# vca.net
KiCad netlist of a schematic drawn in EAGLE
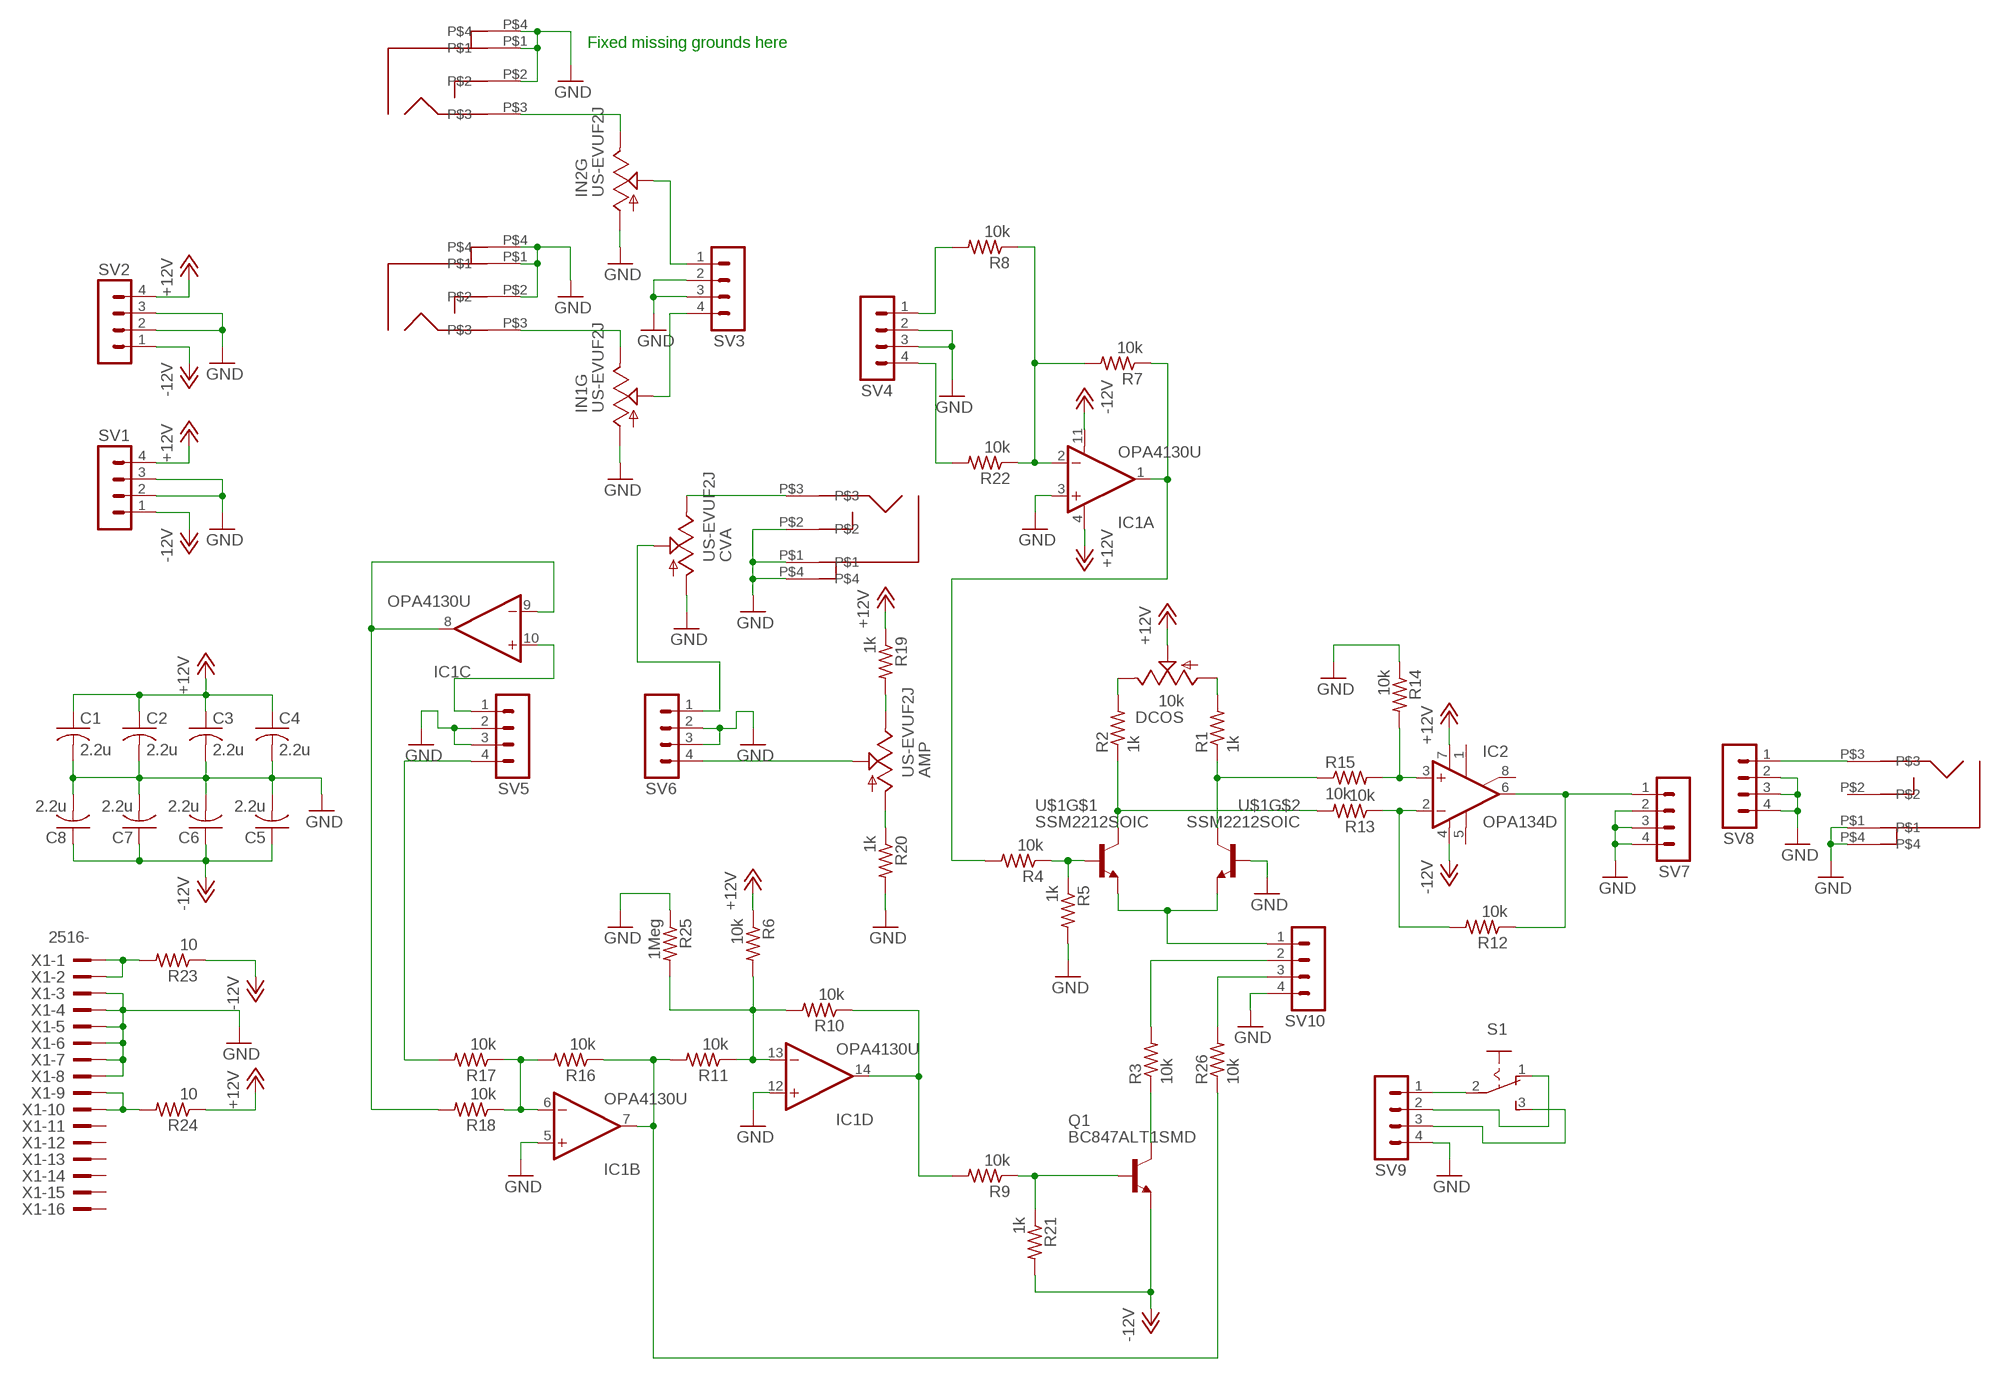
[diagram p0: schematic, sheet 1]

(export (version "E")
  (design (tool "Eeschema 10.0.6"))
  (components
    (comp (ref "AMP")
      (value "US-EVUF2J")
      (footprint "eagle-import:EVUFXJ")
      (libsource (lib "eagle-import") (part "US-EVUF2J"))
    )
    (comp (ref "C1")
      (value "2.2u")
      (footprint "eagle-import:C0603")
      (libsource (lib "eagle-import") (part "C-USC0603"))
    )
    (comp (ref "C2")
      (value "2.2u")
      (footprint "eagle-import:C0603")
      (libsource (lib "eagle-import") (part "C-USC0603"))
    )
    (comp (ref "C3")
      (value "2.2u")
      (footprint "eagle-import:C0603")
      (libsource (lib "eagle-import") (part "C-USC0603"))
    )
    (comp (ref "C4")
      (value "2.2u")
      (footprint "eagle-import:C0603")
      (libsource (lib "eagle-import") (part "C-USC0603"))
    )
    (comp (ref "C5")
      (value "2.2u")
      (footprint "eagle-import:C0603")
      (libsource (lib "eagle-import") (part "C-USC0603"))
    )
    (comp (ref "C6")
      (value "2.2u")
      (footprint "eagle-import:C0603")
      (libsource (lib "eagle-import") (part "C-USC0603"))
    )
    (comp (ref "C7")
      (value "2.2u")
      (footprint "eagle-import:C0603")
      (libsource (lib "eagle-import") (part "C-USC0603"))
    )
    (comp (ref "C8")
      (value "2.2u")
      (footprint "eagle-import:C0603")
      (libsource (lib "eagle-import") (part "C-USC0603"))
    )
    (comp (ref "CVA")
      (value "US-EVUF2J")
      (footprint "eagle-import:EVUFXJ")
      (libsource (lib "eagle-import") (part "US-EVUF2J"))
    )
    (comp (ref "CVIN")
      (value "PJ301BM")
      (footprint "eagle-import:PJ301BM")
      (libsource (lib "eagle-import") (part "PJ301BM"))
    )
    (comp (ref "DCOS")
      (value "10k")
      (footprint "eagle-import:RJ9W")
      (libsource (lib "eagle-import") (part "TRIM_US-RJ9W"))
    )
    (comp (ref "IC1")
      (value "OPA4130U")
      (footprint "eagle-import:SO14")
      (fields (field (name "MF") "TEXAS INSTRUMENTS") (field (name "MPN") "OPA4130UA"))
      (libsource (lib "eagle-import") (part "OPA4130U"))
    )
    (comp (ref "IC2")
      (value "OPA134D")
      (footprint "eagle-import:SO08")
      (libsource (lib "eagle-import") (part "OPA134D"))
    )
    (comp (ref "IN1")
      (value "PJ301BM")
      (footprint "eagle-import:PJ301BM")
      (libsource (lib "eagle-import") (part "PJ301BM"))
    )
    (comp (ref "IN1G")
      (value "US-EVUF2J")
      (footprint "eagle-import:EVUFXJ")
      (libsource (lib "eagle-import") (part "US-EVUF2J"))
    )
    (comp (ref "IN2")
      (value "PJ301BM")
      (footprint "eagle-import:PJ301BM")
      (libsource (lib "eagle-import") (part "PJ301BM"))
    )
    (comp (ref "IN2G")
      (value "US-EVUF2J")
      (footprint "eagle-import:EVUFXJ")
      (libsource (lib "eagle-import") (part "US-EVUF2J"))
    )
    (comp (ref "OUT")
      (value "PJ301BM")
      (footprint "eagle-import:PJ301BM")
      (libsource (lib "eagle-import") (part "PJ301BM"))
    )
    (comp (ref "Q1")
      (value "BC847ALT1SMD")
      (footprint "eagle-import:SOT23")
      (libsource (lib "eagle-import") (part "BC847SMDALT1"))
    )
    (comp (ref "R1")
      (value "1k")
      (footprint "eagle-import:R0603")
      (libsource (lib "eagle-import") (part "R-US_R0603"))
    )
    (comp (ref "R2")
      (value "1k")
      (footprint "eagle-import:R0603")
      (libsource (lib "eagle-import") (part "R-US_R0603"))
    )
    (comp (ref "R3")
      (value "10k")
      (footprint "eagle-import:R0603")
      (libsource (lib "eagle-import") (part "R-US_R0603"))
    )
    (comp (ref "R4")
      (value "10k")
      (footprint "eagle-import:R0603")
      (libsource (lib "eagle-import") (part "R-US_R0603"))
    )
    (comp (ref "R5")
      (value "1k")
      (footprint "eagle-import:R0603")
      (libsource (lib "eagle-import") (part "R-US_R0603"))
    )
    (comp (ref "R6")
      (value "10k")
      (footprint "eagle-import:R0603")
      (libsource (lib "eagle-import") (part "R-US_R0603"))
    )
    (comp (ref "R7")
      (value "10k")
      (footprint "eagle-import:R0603")
      (libsource (lib "eagle-import") (part "R-US_R0603"))
    )
    (comp (ref "R8")
      (value "10k")
      (footprint "eagle-import:R0603")
      (libsource (lib "eagle-import") (part "R-US_R0603"))
    )
    (comp (ref "R9")
      (value "10k")
      (footprint "eagle-import:R0603")
      (libsource (lib "eagle-import") (part "R-US_R0603"))
    )
    (comp (ref "R10")
      (value "10k")
      (footprint "eagle-import:R0603")
      (libsource (lib "eagle-import") (part "R-US_R0603"))
    )
    (comp (ref "R11")
      (value "10k")
      (footprint "eagle-import:R0603")
      (libsource (lib "eagle-import") (part "R-US_R0603"))
    )
    (comp (ref "R12")
      (value "10k")
      (footprint "eagle-import:R0603")
      (libsource (lib "eagle-import") (part "R-US_R0603"))
    )
    (comp (ref "R13")
      (value "10k")
      (footprint "eagle-import:R0603")
      (libsource (lib "eagle-import") (part "R-US_R0603"))
    )
    (comp (ref "R14")
      (value "10k")
      (footprint "eagle-import:R0603")
      (libsource (lib "eagle-import") (part "R-US_R0603"))
    )
    (comp (ref "R15")
      (value "10k")
      (footprint "eagle-import:R0603")
      (libsource (lib "eagle-import") (part "R-US_R0603"))
    )
    (comp (ref "R16")
      (value "10k")
      (footprint "eagle-import:R0603")
      (libsource (lib "eagle-import") (part "R-US_R0603"))
    )
    (comp (ref "R17")
      (value "10k")
      (footprint "eagle-import:R0603")
      (libsource (lib "eagle-import") (part "R-US_R0603"))
    )
    (comp (ref "R18")
      (value "10k")
      (footprint "eagle-import:R0603")
      (libsource (lib "eagle-import") (part "R-US_R0603"))
    )
    (comp (ref "R19")
      (value "1k")
      (footprint "eagle-import:R0603")
      (libsource (lib "eagle-import") (part "R-US_R0603"))
    )
    (comp (ref "R20")
      (value "1k")
      (footprint "eagle-import:R0603")
      (libsource (lib "eagle-import") (part "R-US_R0603"))
    )
    (comp (ref "R21")
      (value "1k")
      (footprint "eagle-import:R0603")
      (libsource (lib "eagle-import") (part "R-US_R0603"))
    )
    (comp (ref "R22")
      (value "10k")
      (footprint "eagle-import:R0603")
      (libsource (lib "eagle-import") (part "R-US_R0603"))
    )
    (comp (ref "R23")
      (value "10")
      (footprint "eagle-import:R0603")
      (libsource (lib "eagle-import") (part "R-US_R0603"))
    )
    (comp (ref "R24")
      (value "10")
      (footprint "eagle-import:R0603")
      (libsource (lib "eagle-import") (part "R-US_R0603"))
    )
    (comp (ref "R25")
      (value "1Meg")
      (footprint "eagle-import:R0603")
      (libsource (lib "eagle-import") (part "R-US_R0603"))
    )
    (comp (ref "R26")
      (value "10k")
      (footprint "eagle-import:R0603")
      (libsource (lib "eagle-import") (part "R-US_R0603"))
    )
    (comp (ref "S1")
      (value "255SB")
      (footprint "eagle-import:255SB")
      (libsource (lib "eagle-import") (part "255SB"))
    )
    (comp (ref "SV1")
      (value "MA04-1")
      (footprint "eagle-import:MA04-1")
      (libsource (lib "eagle-import") (part "MA04-1"))
    )
    (comp (ref "SV2")
      (value "MA04-1")
      (footprint "eagle-import:MA04-1")
      (libsource (lib "eagle-import") (part "MA04-1"))
    )
    (comp (ref "SV3")
      (value "MA04-1")
      (footprint "eagle-import:MA04-1")
      (libsource (lib "eagle-import") (part "MA04-1"))
    )
    (comp (ref "SV4")
      (value "MA04-1")
      (footprint "eagle-import:MA04-1")
      (libsource (lib "eagle-import") (part "MA04-1"))
    )
    (comp (ref "SV5")
      (value "MA04-1")
      (footprint "eagle-import:MA04-1")
      (libsource (lib "eagle-import") (part "MA04-1"))
    )
    (comp (ref "SV6")
      (value "MA04-1")
      (footprint "eagle-import:MA04-1")
      (libsource (lib "eagle-import") (part "MA04-1"))
    )
    (comp (ref "SV7")
      (value "MA04-1")
      (footprint "eagle-import:MA04-1")
      (libsource (lib "eagle-import") (part "MA04-1"))
    )
    (comp (ref "SV8")
      (value "MA04-1")
      (footprint "eagle-import:MA04-1")
      (libsource (lib "eagle-import") (part "MA04-1"))
    )
    (comp (ref "SV9")
      (value "MA04-1")
      (footprint "eagle-import:MA04-1")
      (libsource (lib "eagle-import") (part "MA04-1"))
    )
    (comp (ref "SV10")
      (value "MA04-1")
      (footprint "eagle-import:MA04-1")
      (libsource (lib "eagle-import") (part "MA04-1"))
    )
    (comp (ref "U$1")
      (value "SSM2212SOIC")
      (footprint "eagle-import:SO08")
      (libsource (lib "eagle-import") (part "SSM2212SOIC"))
    )
    (comp (ref "X1")
      (value "2516-")
      (footprint "eagle-import:PAK100_2500-16")
      (libsource (lib "eagle-import") (part "2516-"))
    )
  )
  (nets
    (net (code "1") (name "+12V") (class "Default")
      (node (ref "C1") (pin "1") (pinfunction "1_1") (pintype "passive"))
      (node (ref "C2") (pin "1") (pinfunction "1_1") (pintype "passive"))
      (node (ref "C3") (pin "1") (pinfunction "1_1") (pintype "passive"))
      (node (ref "C4") (pin "1") (pinfunction "1_1") (pintype "passive"))
      (node (ref "DCOS") (pin "S") (pinfunction "S_S") (pintype "passive"))
      (node (ref "IC1") (pin "4") (pinfunction "V+_4") (pintype "power_in"))
      (node (ref "IC2") (pin "7") (pinfunction "V+_7") (pintype "power_in"))
      (node (ref "R19") (pin "1") (pinfunction "1_1") (pintype "passive"))
      (node (ref "R24") (pin "1") (pinfunction "1_1") (pintype "passive"))
      (node (ref "R6") (pin "1") (pinfunction "1_1") (pintype "passive"))
      (node (ref "SV1") (pin "4") (pinfunction "4_4") (pintype "passive"))
      (node (ref "SV2") (pin "4") (pinfunction "4_4") (pintype "passive"))
    )
    (net (code "2") (name "-12V") (class "Default")
      (node (ref "C5") (pin "1") (pinfunction "1_1") (pintype "passive"))
      (node (ref "C6") (pin "1") (pinfunction "1_1") (pintype "passive"))
      (node (ref "C7") (pin "1") (pinfunction "1_1") (pintype "passive"))
      (node (ref "C8") (pin "1") (pinfunction "1_1") (pintype "passive"))
      (node (ref "IC1") (pin "11") (pinfunction "V-_11") (pintype "power_in"))
      (node (ref "IC2") (pin "4") (pinfunction "V-_4") (pintype "power_in"))
      (node (ref "Q1") (pin "2") (pinfunction "E_2") (pintype "passive"))
      (node (ref "R21") (pin "2") (pinfunction "2_2") (pintype "passive"))
      (node (ref "R23") (pin "1") (pinfunction "1_1") (pintype "passive"))
      (node (ref "SV1") (pin "1") (pinfunction "1_1") (pintype "passive"))
      (node (ref "SV2") (pin "1") (pinfunction "1_1") (pintype "passive"))
    )
    (net (code "3") (name "GND") (class "Default")
      (node (ref "C1") (pin "2") (pinfunction "2_2") (pintype "passive"))
      (node (ref "C2") (pin "2") (pinfunction "2_2") (pintype "passive"))
      (node (ref "C3") (pin "2") (pinfunction "2_2") (pintype "passive"))
      (node (ref "C4") (pin "2") (pinfunction "2_2") (pintype "passive"))
      (node (ref "C5") (pin "2") (pinfunction "2_2") (pintype "passive"))
      (node (ref "C6") (pin "2") (pinfunction "2_2") (pintype "passive"))
      (node (ref "C7") (pin "2") (pinfunction "2_2") (pintype "passive"))
      (node (ref "C8") (pin "2") (pinfunction "2_2") (pintype "passive"))
      (node (ref "CVA") (pin "1") (pinfunction "A_1") (pintype "passive"))
      (node (ref "CVIN") (pin "P$1") (pinfunction "P$1_P$1") (pintype "bidirectional"))
      (node (ref "CVIN") (pin "P$2") (pinfunction "P$2_P$2") (pintype "bidirectional"))
      (node (ref "CVIN") (pin "P$4") (pinfunction "P$4_P$4") (pintype "bidirectional"))
      (node (ref "IC1") (pin "12") (pinfunction "+IN_12") (pintype "input"))
      (node (ref "IC1") (pin "3") (pinfunction "+IN_3") (pintype "input"))
      (node (ref "IC1") (pin "5") (pinfunction "+IN_5") (pintype "input"))
      (node (ref "IN1") (pin "P$1") (pinfunction "P$1_P$1") (pintype "bidirectional"))
      (node (ref "IN1") (pin "P$2") (pinfunction "P$2_P$2") (pintype "bidirectional"))
      (node (ref "IN1") (pin "P$4") (pinfunction "P$4_P$4") (pintype "bidirectional"))
      (node (ref "IN1G") (pin "1") (pinfunction "A_1") (pintype "passive"))
      (node (ref "IN2") (pin "P$1") (pinfunction "P$1_P$1") (pintype "bidirectional"))
      (node (ref "IN2") (pin "P$2") (pinfunction "P$2_P$2") (pintype "bidirectional"))
      (node (ref "IN2") (pin "P$4") (pinfunction "P$4_P$4") (pintype "bidirectional"))
      (node (ref "IN2G") (pin "1") (pinfunction "A_1") (pintype "passive"))
      (node (ref "OUT") (pin "P$1") (pinfunction "P$1_P$1") (pintype "bidirectional"))
      (node (ref "OUT") (pin "P$4") (pinfunction "P$4_P$4") (pintype "bidirectional"))
      (node (ref "R14") (pin "1") (pinfunction "1_1") (pintype "passive"))
      (node (ref "R20") (pin "2") (pinfunction "2_2") (pintype "passive"))
      (node (ref "R25") (pin "1") (pinfunction "1_1") (pintype "passive"))
      (node (ref "R5") (pin "2") (pinfunction "2_2") (pintype "passive"))
      (node (ref "SV1") (pin "2") (pinfunction "2_2") (pintype "passive"))
      (node (ref "SV1") (pin "3") (pinfunction "3_3") (pintype "passive"))
      (node (ref "SV10") (pin "4") (pinfunction "4_4") (pintype "passive"))
      (node (ref "SV2") (pin "2") (pinfunction "2_2") (pintype "passive"))
      (node (ref "SV2") (pin "3") (pinfunction "3_3") (pintype "passive"))
      (node (ref "SV3") (pin "2") (pinfunction "2_2") (pintype "passive"))
      (node (ref "SV3") (pin "3") (pinfunction "3_3") (pintype "passive"))
      (node (ref "SV4") (pin "2") (pinfunction "2_2") (pintype "passive"))
      (node (ref "SV4") (pin "3") (pinfunction "3_3") (pintype "passive"))
      (node (ref "SV5") (pin "2") (pinfunction "2_2") (pintype "passive"))
      (node (ref "SV5") (pin "3") (pinfunction "3_3") (pintype "passive"))
      (node (ref "SV6") (pin "2") (pinfunction "2_2") (pintype "passive"))
      (node (ref "SV6") (pin "3") (pinfunction "3_3") (pintype "passive"))
      (node (ref "SV7") (pin "2") (pinfunction "2_2") (pintype "passive"))
      (node (ref "SV7") (pin "3") (pinfunction "3_3") (pintype "passive"))
      (node (ref "SV7") (pin "4") (pinfunction "4_4") (pintype "passive"))
      (node (ref "SV8") (pin "2") (pinfunction "2_2") (pintype "passive"))
      (node (ref "SV8") (pin "3") (pinfunction "3_3") (pintype "passive"))
      (node (ref "SV8") (pin "4") (pinfunction "4_4") (pintype "passive"))
      (node (ref "SV9") (pin "4") (pinfunction "4_4") (pintype "passive"))
      (node (ref "U$1") (pin "7") (pinfunction "B_7") (pintype "passive"))
      (node (ref "X1") (pin "3") (pinfunction "KL_3") (pintype "passive"))
      (node (ref "X1") (pin "4") (pinfunction "KL_4") (pintype "passive"))
      (node (ref "X1") (pin "5") (pinfunction "KL_5") (pintype "passive"))
      (node (ref "X1") (pin "6") (pinfunction "KL_6") (pintype "passive"))
      (node (ref "X1") (pin "7") (pinfunction "KL_7") (pintype "passive"))
      (node (ref "X1") (pin "8") (pinfunction "KL_8") (pintype "passive"))
    )
    (net (code "4") (name "Net-(AMP-A)") (class "Default")
      (node (ref "AMP") (pin "1") (pinfunction "A_1") (pintype "passive"))
      (node (ref "R20") (pin "1") (pinfunction "1_1") (pintype "passive"))
    )
    (net (code "5") (name "Net-(AMP-E)") (class "Default")
      (node (ref "AMP") (pin "3") (pinfunction "E_3") (pintype "passive"))
      (node (ref "R19") (pin "2") (pinfunction "2_2") (pintype "passive"))
    )
    (net (code "6") (name "Net-(AMP-S)") (class "Default")
      (node (ref "AMP") (pin "2") (pinfunction "S_2") (pintype "passive"))
      (node (ref "SV6") (pin "4") (pinfunction "4_4") (pintype "passive"))
    )
    (net (code "7") (name "Net-(CVA-E)") (class "Default")
      (node (ref "CVA") (pin "3") (pinfunction "E_3") (pintype "passive"))
      (node (ref "CVIN") (pin "P$3") (pinfunction "P$3_P$3") (pintype "bidirectional"))
    )
    (net (code "8") (name "Net-(CVA-S)") (class "Default")
      (node (ref "CVA") (pin "2") (pinfunction "S_2") (pintype "passive"))
      (node (ref "SV6") (pin "1") (pinfunction "1_1") (pintype "passive"))
    )
    (net (code "9") (name "Net-(DCOS-PadA)") (class "Default")
      (node (ref "DCOS") (pin "A") (pinfunction "A_A") (pintype "passive"))
      (node (ref "R1") (pin "2") (pinfunction "2_2") (pintype "passive"))
    )
    (net (code "10") (name "Net-(DCOS-PadE)") (class "Default")
      (node (ref "DCOS") (pin "E") (pinfunction "E_E") (pintype "passive"))
      (node (ref "R2") (pin "2") (pinfunction "2_2") (pintype "passive"))
    )
    (net (code "11") (name "Net-(IC1A--IN)") (class "Default")
      (node (ref "IC1") (pin "2") (pinfunction "-IN_2") (pintype "input"))
      (node (ref "R22") (pin "1") (pinfunction "1_1") (pintype "passive"))
      (node (ref "R7") (pin "2") (pinfunction "2_2") (pintype "passive"))
      (node (ref "R8") (pin "1") (pinfunction "1_1") (pintype "passive"))
    )
    (net (code "12") (name "Net-(IC1A-OUT)") (class "Default")
      (node (ref "IC1") (pin "1") (pinfunction "OUT_1") (pintype "output"))
      (node (ref "R4") (pin "2") (pinfunction "2_2") (pintype "passive"))
      (node (ref "R7") (pin "1") (pinfunction "1_1") (pintype "passive"))
    )
    (net (code "13") (name "Net-(IC1B--IN)") (class "Default")
      (node (ref "IC1") (pin "6") (pinfunction "-IN_6") (pintype "input"))
      (node (ref "R16") (pin "2") (pinfunction "2_2") (pintype "passive"))
      (node (ref "R17") (pin "1") (pinfunction "1_1") (pintype "passive"))
      (node (ref "R18") (pin "1") (pinfunction "1_1") (pintype "passive"))
    )
    (net (code "14") (name "Net-(IC1B-OUT)") (class "Default")
      (node (ref "IC1") (pin "7") (pinfunction "OUT_7") (pintype "output"))
      (node (ref "R11") (pin "2") (pinfunction "2_2") (pintype "passive"))
      (node (ref "R16") (pin "1") (pinfunction "1_1") (pintype "passive"))
      (node (ref "R26") (pin "1") (pinfunction "1_1") (pintype "passive"))
    )
    (net (code "15") (name "Net-(IC1C-+IN)") (class "Default")
      (node (ref "IC1") (pin "10") (pinfunction "+IN_10") (pintype "input"))
      (node (ref "SV5") (pin "1") (pinfunction "1_1") (pintype "passive"))
    )
    (net (code "16") (name "Net-(IC1C--IN)") (class "Default")
      (node (ref "IC1") (pin "8") (pinfunction "OUT_8") (pintype "output"))
      (node (ref "IC1") (pin "9") (pinfunction "-IN_9") (pintype "input"))
      (node (ref "R18") (pin "2") (pinfunction "2_2") (pintype "passive"))
    )
    (net (code "17") (name "Net-(IC1D--IN)") (class "Default")
      (node (ref "IC1") (pin "13") (pinfunction "-IN_13") (pintype "input"))
      (node (ref "R10") (pin "2") (pinfunction "2_2") (pintype "passive"))
      (node (ref "R11") (pin "1") (pinfunction "1_1") (pintype "passive"))
      (node (ref "R25") (pin "2") (pinfunction "2_2") (pintype "passive"))
      (node (ref "R6") (pin "2") (pinfunction "2_2") (pintype "passive"))
    )
    (net (code "18") (name "Net-(IC1D-OUT)") (class "Default")
      (node (ref "IC1") (pin "14") (pinfunction "OUT_14") (pintype "output"))
      (node (ref "R10") (pin "1") (pinfunction "1_1") (pintype "passive"))
      (node (ref "R9") (pin "2") (pinfunction "2_2") (pintype "passive"))
    )
    (net (code "19") (name "Net-(IC2-+IN)") (class "Default")
      (node (ref "IC2") (pin "3") (pinfunction "+IN_3") (pintype "input"))
      (node (ref "R14") (pin "2") (pinfunction "2_2") (pintype "passive"))
      (node (ref "R15") (pin "2") (pinfunction "2_2") (pintype "passive"))
    )
    (net (code "20") (name "Net-(IC2--IN)") (class "Default")
      (node (ref "IC2") (pin "2") (pinfunction "-IN_2") (pintype "input"))
      (node (ref "R12") (pin "2") (pinfunction "2_2") (pintype "passive"))
      (node (ref "R13") (pin "1") (pinfunction "1_1") (pintype "passive"))
    )
    (net (code "21") (name "Net-(IC2-OUT)") (class "Default")
      (node (ref "IC2") (pin "6") (pinfunction "OUT_6") (pintype "output"))
      (node (ref "R12") (pin "1") (pinfunction "1_1") (pintype "passive"))
      (node (ref "SV7") (pin "1") (pinfunction "1_1") (pintype "passive"))
    )
    (net (code "22") (name "Net-(IN1G-E)") (class "Default")
      (node (ref "IN1") (pin "P$3") (pinfunction "P$3_P$3") (pintype "bidirectional"))
      (node (ref "IN1G") (pin "3") (pinfunction "E_3") (pintype "passive"))
    )
    (net (code "23") (name "Net-(IN1G-S)") (class "Default")
      (node (ref "IN1G") (pin "2") (pinfunction "S_2") (pintype "passive"))
      (node (ref "SV3") (pin "4") (pinfunction "4_4") (pintype "passive"))
    )
    (net (code "24") (name "Net-(IN2G-E)") (class "Default")
      (node (ref "IN2") (pin "P$3") (pinfunction "P$3_P$3") (pintype "bidirectional"))
      (node (ref "IN2G") (pin "3") (pinfunction "E_3") (pintype "passive"))
    )
    (net (code "25") (name "Net-(IN2G-S)") (class "Default")
      (node (ref "IN2G") (pin "2") (pinfunction "S_2") (pintype "passive"))
      (node (ref "SV3") (pin "1") (pinfunction "1_1") (pintype "passive"))
    )
    (net (code "26") (name "Net-(OUT-PadP$3)") (class "Default")
      (node (ref "OUT") (pin "P$3") (pinfunction "P$3_P$3") (pintype "bidirectional"))
      (node (ref "SV8") (pin "1") (pinfunction "1_1") (pintype "passive"))
    )
    (net (code "27") (name "Net-(Q1-B)") (class "Default")
      (node (ref "Q1") (pin "1") (pinfunction "B_1") (pintype "passive"))
      (node (ref "R21") (pin "1") (pinfunction "1_1") (pintype "passive"))
      (node (ref "R9") (pin "1") (pinfunction "1_1") (pintype "passive"))
    )
    (net (code "28") (name "Net-(Q1-C)") (class "Default")
      (node (ref "Q1") (pin "3") (pinfunction "C_3") (pintype "passive"))
      (node (ref "R3") (pin "1") (pinfunction "1_1") (pintype "passive"))
    )
    (net (code "29") (name "Net-(R3-Pad2)") (class "Default")
      (node (ref "R3") (pin "2") (pinfunction "2_2") (pintype "passive"))
      (node (ref "SV10") (pin "2") (pinfunction "2_2") (pintype "passive"))
    )
    (net (code "30") (name "Net-(R8-Pad2)") (class "Default")
      (node (ref "R8") (pin "2") (pinfunction "2_2") (pintype "passive"))
      (node (ref "SV4") (pin "1") (pinfunction "1_1") (pintype "passive"))
    )
    (net (code "31") (name "Net-(R17-Pad2)") (class "Default")
      (node (ref "R17") (pin "2") (pinfunction "2_2") (pintype "passive"))
      (node (ref "SV5") (pin "4") (pinfunction "4_4") (pintype "passive"))
    )
    (net (code "32") (name "Net-(R22-Pad2)") (class "Default")
      (node (ref "R22") (pin "2") (pinfunction "2_2") (pintype "passive"))
      (node (ref "SV4") (pin "4") (pinfunction "4_4") (pintype "passive"))
    )
    (net (code "33") (name "Net-(R26-Pad2)") (class "Default")
      (node (ref "R26") (pin "2") (pinfunction "2_2") (pintype "passive"))
      (node (ref "SV10") (pin "3") (pinfunction "3_3") (pintype "passive"))
    )
    (net (code "34") (name "Net-(S1-O)") (class "Default")
      (node (ref "S1") (pin "1") (pinfunction "O_1") (pintype "passive"))
      (node (ref "SV9") (pin "2") (pinfunction "2_2") (pintype "passive"))
    )
    (net (code "35") (name "Net-(S1-P)") (class "Default")
      (node (ref "S1") (pin "2") (pinfunction "P_2") (pintype "passive"))
      (node (ref "SV9") (pin "1") (pinfunction "1_1") (pintype "passive"))
    )
    (net (code "36") (name "Net-(S1-S)") (class "Default")
      (node (ref "S1") (pin "3") (pinfunction "S_3") (pintype "passive"))
      (node (ref "SV9") (pin "3") (pinfunction "3_3") (pintype "passive"))
    )
    (net (code "37") (name "Net-(U$1A-B)") (class "Default")
      (node (ref "R4") (pin "1") (pinfunction "1_1") (pintype "passive"))
      (node (ref "R5") (pin "1") (pinfunction "1_1") (pintype "passive"))
      (node (ref "U$1") (pin "2") (pinfunction "B_2") (pintype "passive"))
    )
    (net (code "38") (name "Net-(U$1A-C)") (class "Default")
      (node (ref "R13") (pin "2") (pinfunction "2_2") (pintype "passive"))
      (node (ref "R2") (pin "1") (pinfunction "1_1") (pintype "passive"))
      (node (ref "U$1") (pin "1") (pinfunction "C_1") (pintype "passive"))
    )
    (net (code "39") (name "Net-(U$1A-E)") (class "Default")
      (node (ref "SV10") (pin "1") (pinfunction "1_1") (pintype "passive"))
      (node (ref "U$1") (pin "3") (pinfunction "E_3") (pintype "passive"))
      (node (ref "U$1") (pin "6") (pinfunction "E_6") (pintype "passive"))
    )
    (net (code "40") (name "Net-(U$1B-C)") (class "Default")
      (node (ref "R1") (pin "1") (pinfunction "1_1") (pintype "passive"))
      (node (ref "R15") (pin "1") (pinfunction "1_1") (pintype "passive"))
      (node (ref "U$1") (pin "8") (pinfunction "C_8") (pintype "passive"))
    )
    (net (code "41") (name "Net-(X1A-KL)") (class "Default")
      (node (ref "R23") (pin "2") (pinfunction "2_2") (pintype "passive"))
      (node (ref "X1") (pin "1") (pinfunction "KL_1") (pintype "passive"))
      (node (ref "X1") (pin "2") (pinfunction "KL_2") (pintype "passive"))
    )
    (net (code "42") (name "Net-(X1B-KL)") (class "Default")
      (node (ref "R24") (pin "2") (pinfunction "2_2") (pintype "passive"))
      (node (ref "X1") (pin "10") (pinfunction "KL_10") (pintype "passive"))
      (node (ref "X1") (pin "9") (pinfunction "KL_9") (pintype "passive"))
    )
    (net (code "43") (name "unconnected-(IC2-ON1-Pad1)") (class "Default")
      (node (ref "IC2") (pin "1") (pinfunction "ON1_1") (pintype "passive"))
    )
    (net (code "44") (name "unconnected-(IC2-ON2-Pad8)") (class "Default")
      (node (ref "IC2") (pin "8") (pinfunction "ON2_8") (pintype "passive"))
    )
    (net (code "45") (name "unconnected-(IC2-OPT-Pad5)") (class "Default")
      (node (ref "IC2") (pin "5") (pinfunction "OPT_5") (pintype "passive"))
    )
    (net (code "46") (name "unconnected-(OUT-PadP$2)") (class "Default")
      (node (ref "OUT") (pin "P$2") (pinfunction "P$2_P$2") (pintype "bidirectional"))
    )
    (net (code "47") (name "unconnected-(X1C-KL-Pad11)") (class "Default")
      (node (ref "X1") (pin "11") (pinfunction "KL_11") (pintype "passive"))
    )
    (net (code "48") (name "unconnected-(X1D-KL-Pad12)") (class "Default")
      (node (ref "X1") (pin "12") (pinfunction "KL_12") (pintype "passive"))
    )
    (net (code "49") (name "unconnected-(X1E-KL-Pad13)") (class "Default")
      (node (ref "X1") (pin "13") (pinfunction "KL_13") (pintype "passive"))
    )
    (net (code "50") (name "unconnected-(X1F-KL-Pad14)") (class "Default")
      (node (ref "X1") (pin "14") (pinfunction "KL_14") (pintype "passive"))
    )
    (net (code "51") (name "unconnected-(X1G-KL-Pad15)") (class "Default")
      (node (ref "X1") (pin "15") (pinfunction "KL_15") (pintype "passive"))
    )
    (net (code "52") (name "unconnected-(X1H-KL-Pad16)") (class "Default")
      (node (ref "X1") (pin "16") (pinfunction "KL_16") (pintype "passive"))
    )
  )
)
